# V8.net
KiCad netlist of a schematic drawn in Altium Designer
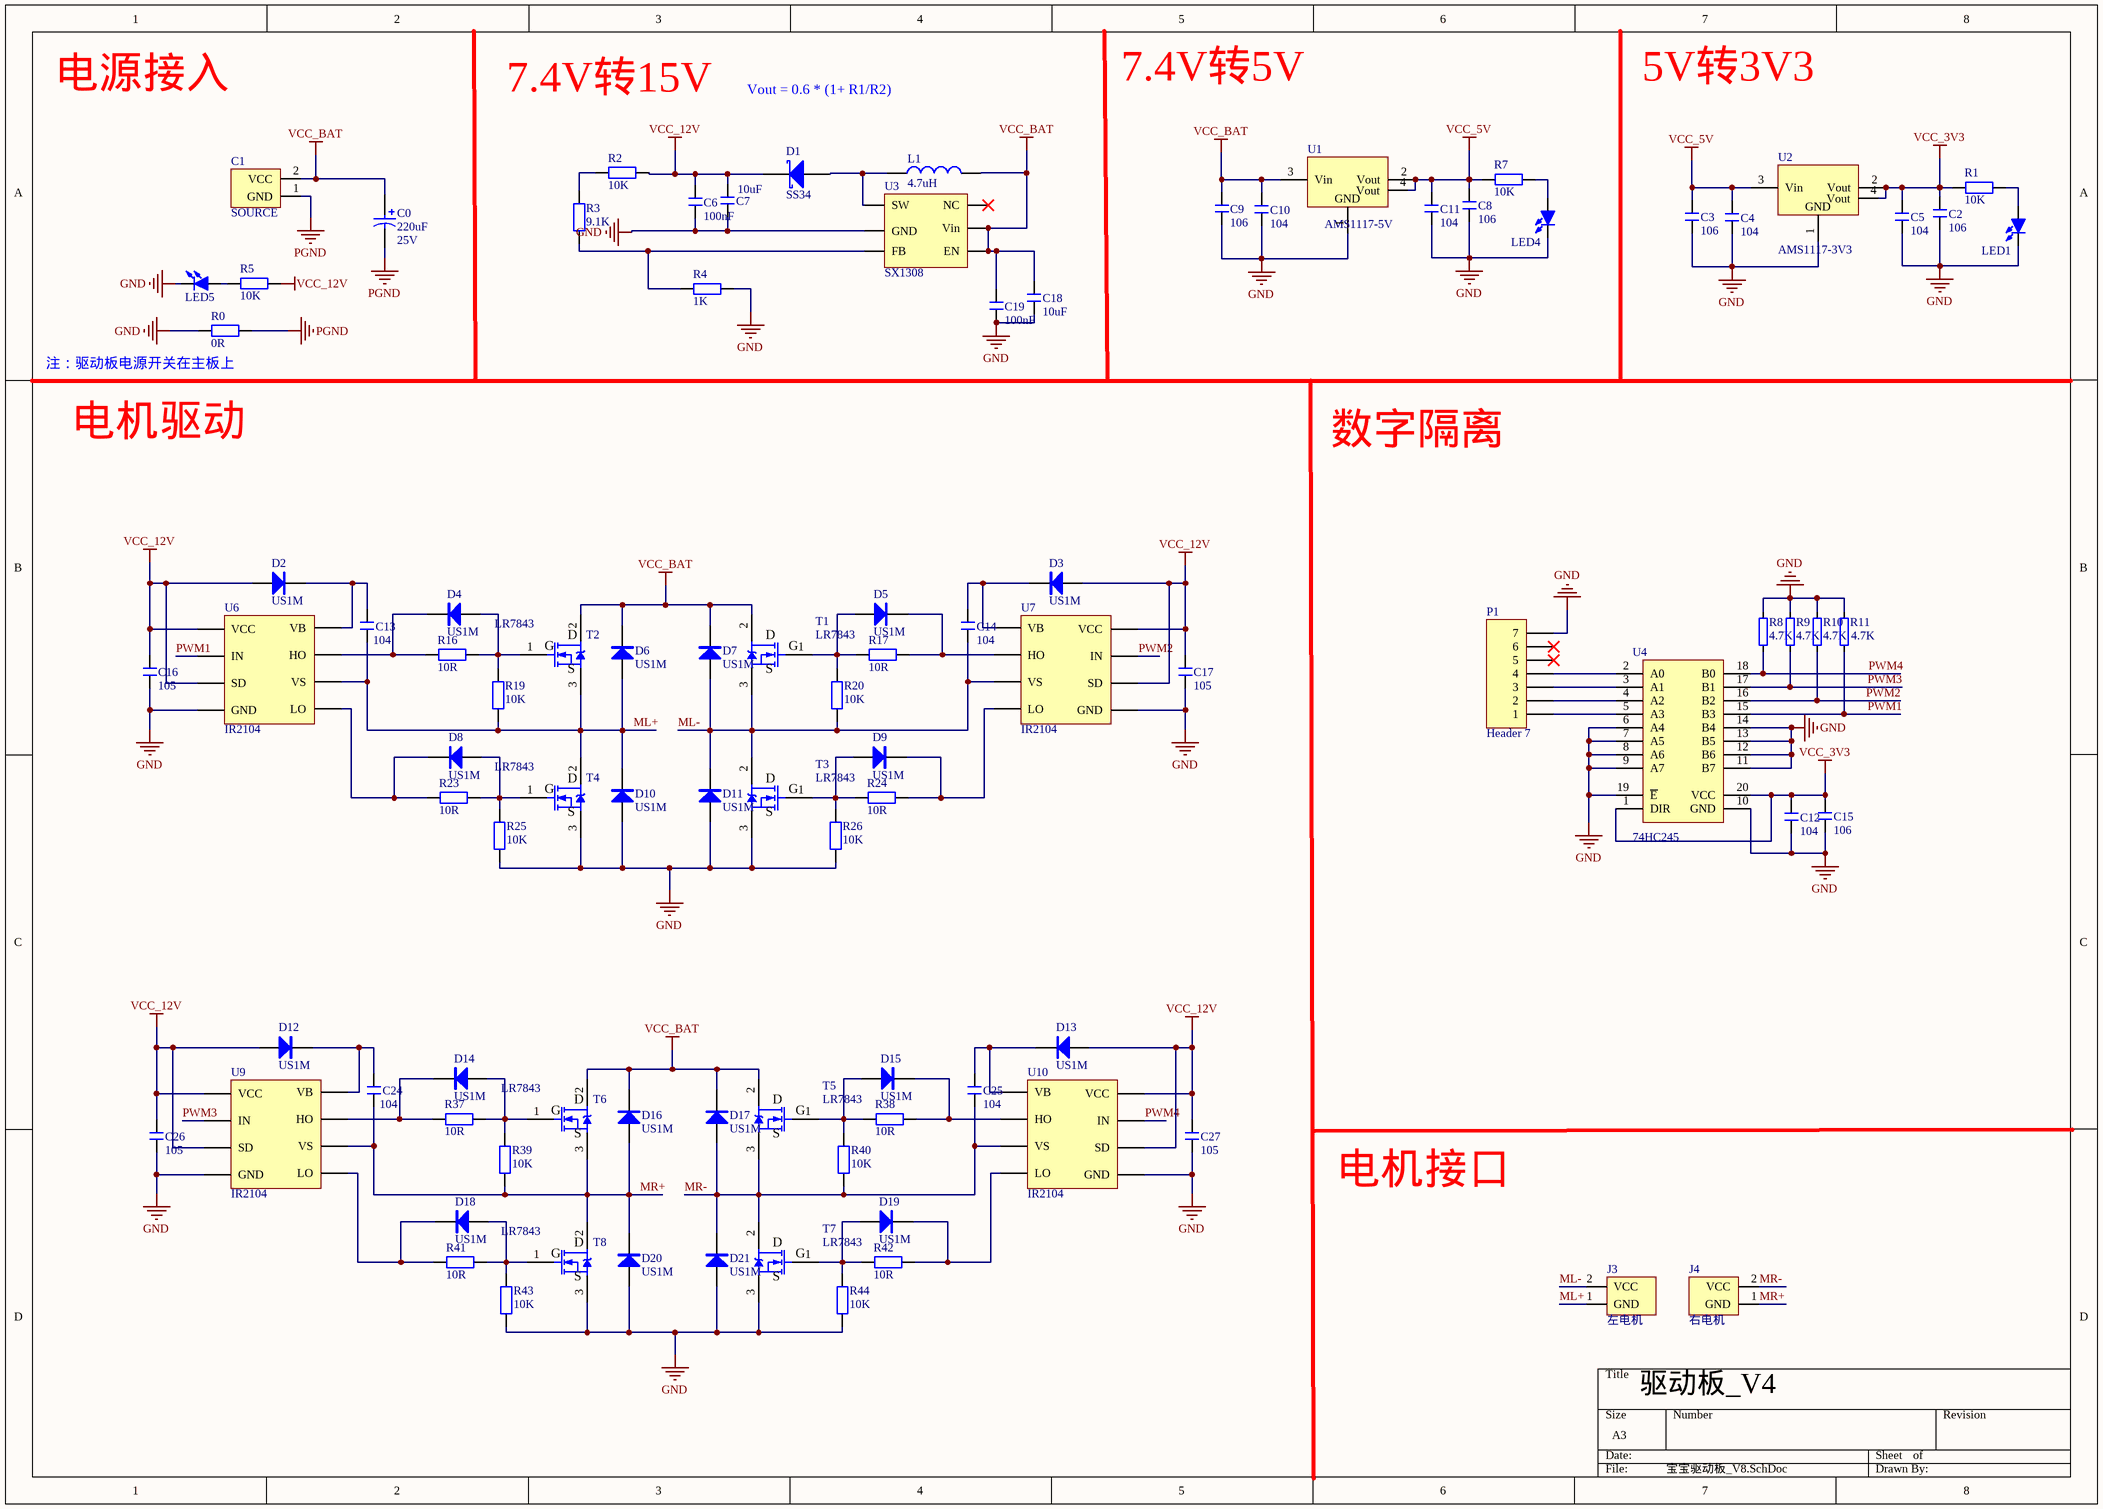
[diagram p0: 宝宝驱动板_V8.SchDoc]

(export (version "E")
  (design (tool "Eeschema 10.0.6"))
  (components
    (comp (ref "C0")
      (value "220uF")
      (footprint "CAPPR3.5-8X11.5")
      (description "Polarized Capacitor (Radial)")
      (fields
        (field (name "VOLTAGE") "25V")
        (field (name "Comment") "220uF 25V")
        (field (name "PUBLISHER") "Altium Limited")
      )
      (libsource (lib "驱动板_V6") (part "Cap-Elect"))
    )
    (comp (ref "C1")
      (value "SOURCE")
      (footprint "KF128-5.08-2P")
      (libsource (lib "飞思-AI原理图库") (part "Source_端子"))
    )
    (comp (ref "C2")
      (value "106")
      (footprint "C 0603_M")
      (description "贴片电容")
      (libsource (lib "视觉原理图库") (part "C"))
    )
    (comp (ref "C3")
      (value "106")
      (footprint "C 0603_M")
      (description "贴片电容")
      (libsource (lib "视觉原理图库") (part "C"))
    )
    (comp (ref "C4")
      (value "104")
      (footprint "C 0603_M")
      (description "贴片电容")
      (libsource (lib "视觉原理图库") (part "C"))
    )
    (comp (ref "C5")
      (value "104")
      (footprint "C 0603_M")
      (description "贴片电容")
      (libsource (lib "视觉原理图库") (part "C"))
    )
    (comp (ref "C6")
      (value "100nF")
      (footprint "C 0603_M")
      (description "贴片电容")
      (libsource (lib "视觉原理图库") (part "C"))
    )
    (comp (ref "C7")
      (value "10uF")
      (footprint "C 0603_M")
      (description "贴片电容")
      (libsource (lib "视觉原理图库") (part "C"))
    )
    (comp (ref "C8")
      (value "106")
      (footprint "C 0603_M")
      (description "贴片电容")
      (libsource (lib "视觉原理图库") (part "C"))
    )
    (comp (ref "C9")
      (value "106")
      (footprint "C 0603_M")
      (description "贴片电容")
      (libsource (lib "视觉原理图库") (part "C"))
    )
    (comp (ref "C10")
      (value "104")
      (footprint "C 0603_M")
      (description "贴片电容")
      (libsource (lib "视觉原理图库") (part "C"))
    )
    (comp (ref "C11")
      (value "104")
      (footprint "C 0603_M")
      (description "贴片电容")
      (libsource (lib "视觉原理图库") (part "C"))
    )
    (comp (ref "C12")
      (value "104")
      (footprint "C 0603_M")
      (description "贴片电容")
      (libsource (lib "视觉原理图库") (part "C"))
    )
    (comp (ref "C13")
      (value "104")
      (footprint "C 0603_M")
      (description "贴片陶瓷电容 MLCC")
      (libsource (lib "视觉原理图库") (part "C"))
    )
    (comp (ref "C14")
      (value "104")
      (footprint "C 0603_M")
      (description "贴片陶瓷电容 MLCC")
      (libsource (lib "视觉原理图库") (part "C"))
    )
    (comp (ref "C15")
      (value "106")
      (footprint "C 0603_M")
      (description "贴片电容")
      (libsource (lib "视觉原理图库") (part "C"))
    )
    (comp (ref "C16")
      (value "105")
      (footprint "C 0603_M")
      (description "贴片电容")
      (libsource (lib "视觉原理图库") (part "C"))
    )
    (comp (ref "C17")
      (value "105")
      (footprint "C 0603_M")
      (description "贴片电容")
      (libsource (lib "视觉原理图库") (part "C"))
    )
    (comp (ref "C18")
      (value "10uF")
      (footprint "C 0603_M")
      (description "贴片电容")
      (libsource (lib "视觉原理图库") (part "C"))
    )
    (comp (ref "C19")
      (value "100nF")
      (footprint "C 0603_M")
      (description "贴片电容")
      (libsource (lib "视觉原理图库") (part "C"))
    )
    (comp (ref "C24")
      (value "104")
      (footprint "C 0603_M")
      (description "贴片陶瓷电容 MLCC")
      (libsource (lib "视觉原理图库") (part "C"))
    )
    (comp (ref "C25")
      (value "104")
      (footprint "C 0603_M")
      (description "贴片陶瓷电容 MLCC")
      (libsource (lib "视觉原理图库") (part "C"))
    )
    (comp (ref "C26")
      (value "105")
      (footprint "C 0603_M")
      (description "贴片电容")
      (libsource (lib "视觉原理图库") (part "C"))
    )
    (comp (ref "C27")
      (value "105")
      (footprint "C 0603_M")
      (description "贴片电容")
      (libsource (lib "视觉原理图库") (part "C"))
    )
    (comp (ref "D1")
      (value "SS34")
      (footprint "SMA")
      (description "肖特基二极管")
      (libsource (lib "视觉原理图库") (part "SS34"))
    )
    (comp (ref "D2")
      (value "US1M")
      (footprint "SMA")
      (description "快恢复二极管")
      (libsource (lib "视觉原理图库") (part "US1M"))
    )
    (comp (ref "D3")
      (value "US1M")
      (footprint "SMA")
      (description "快恢复二极管")
      (libsource (lib "视觉原理图库") (part "US1M"))
    )
    (comp (ref "D4")
      (value "US1M")
      (footprint "SMA")
      (description "快恢复二极管")
      (libsource (lib "视觉原理图库") (part "US1M"))
    )
    (comp (ref "D5")
      (value "US1M")
      (footprint "SMA")
      (description "快恢复二极管")
      (libsource (lib "视觉原理图库") (part "US1M"))
    )
    (comp (ref "D6")
      (value "US1M")
      (footprint "SMA")
      (description "快恢复二极管")
      (libsource (lib "视觉原理图库") (part "US1M"))
    )
    (comp (ref "D7")
      (value "US1M")
      (footprint "SMA")
      (description "快恢复二极管")
      (libsource (lib "视觉原理图库") (part "US1M"))
    )
    (comp (ref "D8")
      (value "US1M")
      (footprint "SMA")
      (description "快恢复二极管")
      (libsource (lib "视觉原理图库") (part "US1M"))
    )
    (comp (ref "D9")
      (value "US1M")
      (footprint "SMA")
      (description "快恢复二极管")
      (libsource (lib "视觉原理图库") (part "US1M"))
    )
    (comp (ref "D10")
      (value "US1M")
      (footprint "SMA")
      (description "快恢复二极管")
      (libsource (lib "视觉原理图库") (part "US1M"))
    )
    (comp (ref "D11")
      (value "US1M")
      (footprint "SMA")
      (description "快恢复二极管")
      (libsource (lib "视觉原理图库") (part "US1M"))
    )
    (comp (ref "D12")
      (value "US1M")
      (footprint "SMA")
      (description "快恢复二极管")
      (libsource (lib "视觉原理图库") (part "US1M"))
    )
    (comp (ref "D13")
      (value "US1M")
      (footprint "SMA")
      (description "快恢复二极管")
      (libsource (lib "视觉原理图库") (part "US1M"))
    )
    (comp (ref "D14")
      (value "US1M")
      (footprint "SMA")
      (description "快恢复二极管")
      (libsource (lib "视觉原理图库") (part "US1M"))
    )
    (comp (ref "D15")
      (value "US1M")
      (footprint "SMA")
      (description "快恢复二极管")
      (libsource (lib "视觉原理图库") (part "US1M"))
    )
    (comp (ref "D16")
      (value "US1M")
      (footprint "SMA")
      (description "快恢复二极管")
      (libsource (lib "视觉原理图库") (part "US1M"))
    )
    (comp (ref "D17")
      (value "US1M")
      (footprint "SMA")
      (description "快恢复二极管")
      (libsource (lib "视觉原理图库") (part "US1M"))
    )
    (comp (ref "D18")
      (value "US1M")
      (footprint "SMA")
      (description "快恢复二极管")
      (libsource (lib "视觉原理图库") (part "US1M"))
    )
    (comp (ref "D19")
      (value "US1M")
      (footprint "SMA")
      (description "快恢复二极管")
      (libsource (lib "视觉原理图库") (part "US1M"))
    )
    (comp (ref "D20")
      (value "US1M")
      (footprint "SMA")
      (description "快恢复二极管")
      (libsource (lib "视觉原理图库") (part "US1M"))
    )
    (comp (ref "D21")
      (value "US1M")
      (footprint "SMA")
      (description "快恢复二极管")
      (libsource (lib "视觉原理图库") (part "US1M"))
    )
    (comp (ref "J3") (value "左电机") (footprint "KF128-5.08-2P") (libsource (lib "") (part "接线端子_1")))
    (comp (ref "J4") (value "右电机") (footprint "KF128-5.08-2P") (libsource (lib "视觉原理图库") (part "接线端子")))
    (comp (ref "L1")
      (value "4.7uH")
      (footprint "L 7*7")
      (description "功率电感")
      (libsource (lib "视觉原理图库") (part "L"))
    )
    (comp (ref "LED1")
      (value "红色")
      (footprint "LED 0603")
      (description "贴片LED")
      (fields (field (name "版权归属") "封装库来自淘宝 ID：黄晶宝石"))
      (libsource (lib "视觉原理图库") (part "LED"))
    )
    (comp (ref "LED4")
      (value "红色")
      (footprint "LED 0603")
      (description "贴片LED")
      (fields (field (name "版权归属") "封装库来自淘宝 ID：黄晶宝石"))
      (libsource (lib "视觉原理图库") (part "LED"))
    )
    (comp (ref "LED5")
      (value "红色")
      (footprint "LED 0603")
      (description "贴片LED")
      (fields (field (name "版权归属") "封装库来自淘宝 ID：黄晶宝石"))
      (libsource (lib "视觉原理图库") (part "LED"))
    )
    (comp (ref "P1")
      (value "Header 7")
      (footprint "PH2.0-L-Z-7P")
      (description "Header, 7-Pin")
      (fields (field (name "PUBLISHER") "Altium Limited"))
      (libsource (lib "Miscellaneous Connectors") (part "Header 7"))
    )
    (comp (ref "R0")
      (value "0R")
      (footprint "R 2512_M")
      (description "贴片电阻")
      (fields (field (name "Comment") "R") (field (name "版权归属") "电协硬件组"))
      (libsource (lib "3.1   - 电阻-电容-电感") (part "R"))
    )
    (comp (ref "R1")
      (value "10K")
      (footprint "R 0603_M")
      (description "贴片电阻")
      (fields (field (name "版权归属") "来自淘宝 ID：黄晶宝石"))
      (libsource (lib "视觉原理图库") (part "R"))
    )
    (comp (ref "R2")
      (value "10K")
      (footprint "R 0603_M")
      (description "贴片电阻")
      (fields (field (name "版权归属") "来自淘宝 ID：黄晶宝石"))
      (libsource (lib "视觉原理图库") (part "R"))
    )
    (comp (ref "R3")
      (value "9.1K")
      (footprint "R 0603_M")
      (description "贴片电阻")
      (fields (field (name "版权归属") "来自淘宝 ID：黄晶宝石"))
      (libsource (lib "视觉原理图库") (part "R"))
    )
    (comp (ref "R4")
      (value "1K")
      (footprint "R 0603_M")
      (description "贴片电阻")
      (fields (field (name "版权归属") "来自淘宝 ID：黄晶宝石"))
      (libsource (lib "视觉原理图库") (part "R"))
    )
    (comp (ref "R5")
      (value "10K")
      (footprint "R 0603_M")
      (description "贴片电阻")
      (fields (field (name "版权归属") "来自淘宝 ID：黄晶宝石"))
      (libsource (lib "视觉原理图库") (part "R"))
    )
    (comp (ref "R7")
      (value "10K")
      (footprint "R 0603_M")
      (description "贴片电阻")
      (fields (field (name "版权归属") "来自淘宝 ID：黄晶宝石"))
      (libsource (lib "视觉原理图库") (part "R"))
    )
    (comp (ref "R8") (value "4.7K") (footprint "R 0603_M") (libsource (lib "驱动板--原理图") (part "RES")))
    (comp (ref "R9") (value "4.7K") (footprint "R 0603_M") (libsource (lib "驱动板--原理图") (part "RES")))
    (comp (ref "R10") (value "4.7K") (footprint "R 0603_M") (libsource (lib "驱动板--原理图") (part "RES")))
    (comp (ref "R11") (value "4.7K") (footprint "R 0603_M") (libsource (lib "驱动板--原理图") (part "RES")))
    (comp (ref "R16")
      (value "10R")
      (footprint "R 0603_M")
      (description "贴片电阻")
      (fields (field (name "版权归属") "来自淘宝 ID：黄晶宝石"))
      (libsource (lib "视觉原理图库") (part "R"))
    )
    (comp (ref "R17")
      (value "10R")
      (footprint "R 0603_M")
      (description "贴片电阻")
      (fields (field (name "版权归属") "来自淘宝 ID：黄晶宝石"))
      (libsource (lib "视觉原理图库") (part "R"))
    )
    (comp (ref "R19")
      (value "10K")
      (footprint "R 0603_M")
      (description "贴片电阻")
      (fields (field (name "版权归属") "来自淘宝 ID：黄晶宝石"))
      (libsource (lib "视觉原理图库") (part "R"))
    )
    (comp (ref "R20")
      (value "10K")
      (footprint "R 0603_M")
      (description "贴片电阻")
      (fields (field (name "版权归属") "来自淘宝 ID：黄晶宝石"))
      (libsource (lib "视觉原理图库") (part "R"))
    )
    (comp (ref "R23")
      (value "10R")
      (footprint "R 0603_M")
      (description "贴片电阻")
      (fields (field (name "版权归属") "来自淘宝 ID：黄晶宝石"))
      (libsource (lib "视觉原理图库") (part "R"))
    )
    (comp (ref "R24")
      (value "10R")
      (footprint "R 0603_M")
      (description "贴片电阻")
      (fields (field (name "版权归属") "来自淘宝 ID：黄晶宝石"))
      (libsource (lib "视觉原理图库") (part "R"))
    )
    (comp (ref "R25")
      (value "10K")
      (footprint "R 0603_M")
      (description "贴片电阻")
      (fields (field (name "版权归属") "来自淘宝 ID：黄晶宝石"))
      (libsource (lib "视觉原理图库") (part "R"))
    )
    (comp (ref "R26")
      (value "10K")
      (footprint "R 0603_M")
      (description "贴片电阻")
      (fields (field (name "版权归属") "来自淘宝 ID：黄晶宝石"))
      (libsource (lib "视觉原理图库") (part "R"))
    )
    (comp (ref "R37")
      (value "10R")
      (footprint "R 0603_M")
      (description "贴片电阻")
      (fields (field (name "版权归属") "来自淘宝 ID：黄晶宝石"))
      (libsource (lib "视觉原理图库") (part "R"))
    )
    (comp (ref "R38")
      (value "10R")
      (footprint "R 0603_M")
      (description "贴片电阻")
      (fields (field (name "版权归属") "来自淘宝 ID：黄晶宝石"))
      (libsource (lib "视觉原理图库") (part "R"))
    )
    (comp (ref "R39")
      (value "10K")
      (footprint "R 0603_M")
      (description "贴片电阻")
      (fields (field (name "版权归属") "来自淘宝 ID：黄晶宝石"))
      (libsource (lib "视觉原理图库") (part "R"))
    )
    (comp (ref "R40")
      (value "10K")
      (footprint "R 0603_M")
      (description "贴片电阻")
      (fields (field (name "版权归属") "来自淘宝 ID：黄晶宝石"))
      (libsource (lib "视觉原理图库") (part "R"))
    )
    (comp (ref "R41")
      (value "10R")
      (footprint "R 0603_M")
      (description "贴片电阻")
      (fields (field (name "版权归属") "来自淘宝 ID：黄晶宝石"))
      (libsource (lib "视觉原理图库") (part "R"))
    )
    (comp (ref "R42")
      (value "10R")
      (footprint "R 0603_M")
      (description "贴片电阻")
      (fields (field (name "版权归属") "来自淘宝 ID：黄晶宝石"))
      (libsource (lib "视觉原理图库") (part "R"))
    )
    (comp (ref "R43")
      (value "10K")
      (footprint "R 0603_M")
      (description "贴片电阻")
      (fields (field (name "版权归属") "来自淘宝 ID：黄晶宝石"))
      (libsource (lib "视觉原理图库") (part "R"))
    )
    (comp (ref "R44")
      (value "10K")
      (footprint "R 0603_M")
      (description "贴片电阻")
      (fields (field (name "版权归属") "来自淘宝 ID：黄晶宝石"))
      (libsource (lib "视觉原理图库") (part "R"))
    )
    (comp (ref "T1")
      (value "LR7843")
      (footprint "TO252")
      (description "N-MOS")
      (libsource (lib "视觉原理图库") (part "SM3113NSUC"))
    )
    (comp (ref "T2")
      (value "LR7843")
      (footprint "TO252")
      (description "N-MOS")
      (libsource (lib "视觉原理图库") (part "SM3113NSUC"))
    )
    (comp (ref "T3")
      (value "LR7843")
      (footprint "TO252")
      (description "N-MOS")
      (libsource (lib "视觉原理图库") (part "SM3113NSUC"))
    )
    (comp (ref "T4")
      (value "LR7843")
      (footprint "TO252")
      (description "N-MOS")
      (libsource (lib "视觉原理图库") (part "SM3113NSUC"))
    )
    (comp (ref "T5")
      (value "LR7843")
      (footprint "TO252")
      (description "N-MOS")
      (libsource (lib "视觉原理图库") (part "SM3113NSUC"))
    )
    (comp (ref "T6")
      (value "LR7843")
      (footprint "TO252")
      (description "N-MOS")
      (libsource (lib "视觉原理图库") (part "SM3113NSUC"))
    )
    (comp (ref "T7")
      (value "LR7843")
      (footprint "TO252")
      (description "N-MOS")
      (libsource (lib "视觉原理图库") (part "SM3113NSUC"))
    )
    (comp (ref "T8")
      (value "LR7843")
      (footprint "TO252")
      (description "N-MOS")
      (libsource (lib "视觉原理图库") (part "SM3113NSUC"))
    )
    (comp (ref "U1")
      (value "AMS1117-5V")
      (footprint "SOT223_L")
      (description "三端稳压芯片")
      (libsource (lib "视觉原理图库") (part "AMS1117"))
    )
    (comp (ref "U2")
      (value "AMS1117-3V3")
      (footprint "SOT223_L")
      (description "三端稳压芯片")
      (libsource (lib "视觉原理图库") (part "AMS1117"))
    )
    (comp (ref "U3")
      (value "SX1308")
      (footprint "SOT23-6")
      (description "DCDC升压芯片")
      (libsource (lib "视觉原理图库") (part "SX1308"))
    )
    (comp (ref "U4")
      (value "74HC245")
      (footprint "SOP20Z_M")
      (description "光耦隔离")
      (libsource (lib "驱动板_V5") (part "74HC245"))
    )
    (comp (ref "U6")
      (value "IR2104")
      (footprint "SOP8")
      (description "半桥驱动芯片")
      (libsource (lib "视觉原理图库") (part "EG2104"))
    )
    (comp (ref "U7")
      (value "IR2104")
      (footprint "SOP8")
      (description "半桥驱动芯片")
      (libsource (lib "") (part "EG2104_1"))
    )
    (comp (ref "U9")
      (value "IR2104")
      (footprint "SOP8")
      (description "半桥驱动芯片")
      (libsource (lib "视觉原理图库") (part "EG2104"))
    )
    (comp (ref "U10")
      (value "IR2104")
      (footprint "SOP8")
      (description "半桥驱动芯片")
      (libsource (lib "") (part "EG2104_1"))
    )
  )
  (nets
    (net (code "1") (name "/ML+") (class "Default")
      (node (ref "C13") (pin "1") (pinfunction "1_1") (pintype "passive"))
      (node (ref "D10") (pin "2") (pinfunction "K_2") (pintype "passive"))
      (node (ref "D6") (pin "1") (pinfunction "A_1") (pintype "passive"))
      (node (ref "J3") (pin "1") (pinfunction "GND_1") (pintype "passive"))
      (node (ref "R19") (pin "1") (pinfunction "1_1") (pintype "passive"))
      (node (ref "T2") (pin "3") (pinfunction "S_3") (pintype "passive"))
      (node (ref "T4") (pin "2") (pinfunction "D_2") (pintype "passive"))
      (node (ref "U6") (pin "6") (pinfunction "VS_6") (pintype "passive"))
    )
    (net (code "2") (name "/ML-") (class "Default")
      (node (ref "C14") (pin "1") (pinfunction "1_1") (pintype "passive"))
      (node (ref "D11") (pin "2") (pinfunction "K_2") (pintype "passive"))
      (node (ref "D7") (pin "1") (pinfunction "A_1") (pintype "passive"))
      (node (ref "J3") (pin "2") (pinfunction "VCC_2") (pintype "passive"))
      (node (ref "R20") (pin "1") (pinfunction "1_1") (pintype "passive"))
      (node (ref "T1") (pin "3") (pinfunction "S_3") (pintype "passive"))
      (node (ref "T3") (pin "2") (pinfunction "D_2") (pintype "passive"))
      (node (ref "U7") (pin "6") (pinfunction "VS_6") (pintype "passive"))
    )
    (net (code "3") (name "/MR+") (class "Default")
      (node (ref "C24") (pin "1") (pinfunction "1_1") (pintype "passive"))
      (node (ref "D16") (pin "1") (pinfunction "A_1") (pintype "passive"))
      (node (ref "D20") (pin "2") (pinfunction "K_2") (pintype "passive"))
      (node (ref "J4") (pin "1") (pinfunction "GND_1") (pintype "passive"))
      (node (ref "R39") (pin "1") (pinfunction "1_1") (pintype "passive"))
      (node (ref "T6") (pin "3") (pinfunction "S_3") (pintype "passive"))
      (node (ref "T8") (pin "2") (pinfunction "D_2") (pintype "passive"))
      (node (ref "U9") (pin "6") (pinfunction "VS_6") (pintype "passive"))
    )
    (net (code "4") (name "/MR-") (class "Default")
      (node (ref "C25") (pin "1") (pinfunction "1_1") (pintype "passive"))
      (node (ref "D17") (pin "1") (pinfunction "A_1") (pintype "passive"))
      (node (ref "D21") (pin "2") (pinfunction "K_2") (pintype "passive"))
      (node (ref "J4") (pin "2") (pinfunction "VCC_2") (pintype "passive"))
      (node (ref "R40") (pin "1") (pinfunction "1_1") (pintype "passive"))
      (node (ref "T5") (pin "3") (pinfunction "S_3") (pintype "passive"))
      (node (ref "T7") (pin "2") (pinfunction "D_2") (pintype "passive"))
      (node (ref "U10") (pin "6") (pinfunction "VS_6") (pintype "passive"))
    )
    (net (code "5") (name "/PWM1") (class "Default")
      (node (ref "R11") (pin "1") (pinfunction "1_1") (pintype "passive"))
      (node (ref "U4") (pin "15") (pinfunction "B3_15") (pintype "passive"))
      (node (ref "U6") (pin "2") (pinfunction "IN_2") (pintype "passive"))
    )
    (net (code "6") (name "/PWM2") (class "Default")
      (node (ref "R10") (pin "1") (pinfunction "1_1") (pintype "passive"))
      (node (ref "U4") (pin "16") (pinfunction "B2_16") (pintype "passive"))
      (node (ref "U7") (pin "2") (pinfunction "IN_2") (pintype "passive"))
    )
    (net (code "7") (name "/PWM3") (class "Default")
      (node (ref "R9") (pin "1") (pinfunction "1_1") (pintype "passive"))
      (node (ref "U4") (pin "17") (pinfunction "B1_17") (pintype "passive"))
      (node (ref "U9") (pin "2") (pinfunction "IN_2") (pintype "passive"))
    )
    (net (code "8") (name "/PWM4") (class "Default")
      (node (ref "R8") (pin "1") (pinfunction "1_1") (pintype "passive"))
      (node (ref "U10") (pin "2") (pinfunction "IN_2") (pintype "passive"))
      (node (ref "U4") (pin "18") (pinfunction "B0_18") (pintype "passive"))
    )
    (net (code "9") (name "GND") (class "Default")
      (node (ref "C10") (pin "1") (pinfunction "1_1") (pintype "passive"))
      (node (ref "C11") (pin "1") (pinfunction "1_1") (pintype "passive"))
      (node (ref "C12") (pin "1") (pinfunction "1_1") (pintype "passive"))
      (node (ref "C15") (pin "1") (pinfunction "1_1") (pintype "passive"))
      (node (ref "C16") (pin "1") (pinfunction "1_1") (pintype "passive"))
      (node (ref "C17") (pin "1") (pinfunction "1_1") (pintype "passive"))
      (node (ref "C18") (pin "1") (pinfunction "1_1") (pintype "passive"))
      (node (ref "C19") (pin "1") (pinfunction "1_1") (pintype "passive"))
      (node (ref "C2") (pin "1") (pinfunction "1_1") (pintype "passive"))
      (node (ref "C26") (pin "1") (pinfunction "1_1") (pintype "passive"))
      (node (ref "C27") (pin "1") (pinfunction "1_1") (pintype "passive"))
      (node (ref "C3") (pin "1") (pinfunction "1_1") (pintype "passive"))
      (node (ref "C4") (pin "1") (pinfunction "1_1") (pintype "passive"))
      (node (ref "C5") (pin "1") (pinfunction "1_1") (pintype "passive"))
      (node (ref "C6") (pin "1") (pinfunction "1_1") (pintype "passive"))
      (node (ref "C7") (pin "1") (pinfunction "1_1") (pintype "passive"))
      (node (ref "C8") (pin "1") (pinfunction "1_1") (pintype "passive"))
      (node (ref "C9") (pin "1") (pinfunction "1_1") (pintype "passive"))
      (node (ref "D10") (pin "1") (pinfunction "A_1") (pintype "passive"))
      (node (ref "D11") (pin "1") (pinfunction "A_1") (pintype "passive"))
      (node (ref "D20") (pin "1") (pinfunction "A_1") (pintype "passive"))
      (node (ref "D21") (pin "1") (pinfunction "A_1") (pintype "passive"))
      (node (ref "LED1") (pin "2") (pinfunction "K_2") (pintype "passive"))
      (node (ref "LED4") (pin "2") (pinfunction "K_2") (pintype "passive"))
      (node (ref "LED5") (pin "2") (pinfunction "K_2") (pintype "passive"))
      (node (ref "P1") (pin "7") (pinfunction "7_7") (pintype "passive"))
      (node (ref "R0") (pin "1") (pinfunction "1_1") (pintype "passive"))
      (node (ref "R10") (pin "2") (pinfunction "2_2") (pintype "passive"))
      (node (ref "R11") (pin "2") (pinfunction "2_2") (pintype "passive"))
      (node (ref "R25") (pin "1") (pinfunction "1_1") (pintype "passive"))
      (node (ref "R26") (pin "1") (pinfunction "1_1") (pintype "passive"))
      (node (ref "R4") (pin "1") (pinfunction "1_1") (pintype "passive"))
      (node (ref "R43") (pin "1") (pinfunction "1_1") (pintype "passive"))
      (node (ref "R44") (pin "1") (pinfunction "1_1") (pintype "passive"))
      (node (ref "R8") (pin "2") (pinfunction "2_2") (pintype "passive"))
      (node (ref "R9") (pin "2") (pinfunction "2_2") (pintype "passive"))
      (node (ref "T3") (pin "3") (pinfunction "S_3") (pintype "passive"))
      (node (ref "T4") (pin "3") (pinfunction "S_3") (pintype "passive"))
      (node (ref "T7") (pin "3") (pinfunction "S_3") (pintype "passive"))
      (node (ref "T8") (pin "3") (pinfunction "S_3") (pintype "passive"))
      (node (ref "U1") (pin "1") (pinfunction "GND_1") (pintype "passive"))
      (node (ref "U10") (pin "4") (pinfunction "GND_4") (pintype "passive"))
      (node (ref "U2") (pin "1") (pinfunction "GND_1") (pintype "passive"))
      (node (ref "U3") (pin "2") (pinfunction "GND_2") (pintype "passive"))
      (node (ref "U4") (pin "10") (pinfunction "GND_10") (pintype "passive"))
      (node (ref "U4") (pin "11") (pinfunction "B7_11") (pintype "passive"))
      (node (ref "U4") (pin "12") (pinfunction "B6_12") (pintype "passive"))
      (node (ref "U4") (pin "13") (pinfunction "B5_13") (pintype "passive"))
      (node (ref "U4") (pin "14") (pinfunction "B4_14") (pintype "passive"))
      (node (ref "U4") (pin "19") (pinfunction "~{E}_19") (pintype "passive"))
      (node (ref "U4") (pin "6") (pinfunction "A4_6") (pintype "passive"))
      (node (ref "U4") (pin "7") (pinfunction "A5_7") (pintype "passive"))
      (node (ref "U4") (pin "8") (pinfunction "A6_8") (pintype "passive"))
      (node (ref "U4") (pin "9") (pinfunction "A7_9") (pintype "passive"))
      (node (ref "U6") (pin "4") (pinfunction "GND_4") (pintype "passive"))
      (node (ref "U7") (pin "4") (pinfunction "GND_4") (pintype "passive"))
      (node (ref "U9") (pin "4") (pinfunction "GND_4") (pintype "passive"))
    )
    (net (code "10") (name "Net-(D1-A)") (class "Default")
      (node (ref "D1") (pin "1") (pinfunction "A_1") (pintype "passive"))
      (node (ref "L1") (pin "1") (pinfunction "1_1") (pintype "passive"))
      (node (ref "U3") (pin "1") (pinfunction "SW_1") (pintype "passive"))
    )
    (net (code "11") (name "Net-(D2-K)") (class "Default")
      (node (ref "C13") (pin "2") (pinfunction "2_2") (pintype "passive"))
      (node (ref "D2") (pin "2") (pinfunction "K_2") (pintype "passive"))
      (node (ref "U6") (pin "8") (pinfunction "VB_8") (pintype "passive"))
    )
    (net (code "12") (name "Net-(D3-K)") (class "Default")
      (node (ref "C14") (pin "2") (pinfunction "2_2") (pintype "passive"))
      (node (ref "D3") (pin "2") (pinfunction "K_2") (pintype "passive"))
      (node (ref "U7") (pin "8") (pinfunction "VB_8") (pintype "passive"))
    )
    (net (code "13") (name "Net-(D4-A)") (class "Default")
      (node (ref "D4") (pin "1") (pinfunction "A_1") (pintype "passive"))
      (node (ref "R16") (pin "2") (pinfunction "2_2") (pintype "passive"))
      (node (ref "R19") (pin "2") (pinfunction "2_2") (pintype "passive"))
      (node (ref "T2") (pin "1") (pinfunction "G_1") (pintype "passive"))
    )
    (net (code "14") (name "Net-(D4-K)") (class "Default")
      (node (ref "D4") (pin "2") (pinfunction "K_2") (pintype "passive"))
      (node (ref "R16") (pin "1") (pinfunction "1_1") (pintype "passive"))
      (node (ref "U6") (pin "7") (pinfunction "HO_7") (pintype "passive"))
    )
    (net (code "15") (name "Net-(D5-A)") (class "Default")
      (node (ref "D5") (pin "1") (pinfunction "A_1") (pintype "passive"))
      (node (ref "R17") (pin "2") (pinfunction "2_2") (pintype "passive"))
      (node (ref "R20") (pin "2") (pinfunction "2_2") (pintype "passive"))
      (node (ref "T1") (pin "1") (pinfunction "G_1") (pintype "passive"))
    )
    (net (code "16") (name "Net-(D5-K)") (class "Default")
      (node (ref "D5") (pin "2") (pinfunction "K_2") (pintype "passive"))
      (node (ref "R17") (pin "1") (pinfunction "1_1") (pintype "passive"))
      (node (ref "U7") (pin "7") (pinfunction "HO_7") (pintype "passive"))
    )
    (net (code "17") (name "Net-(D8-A)") (class "Default")
      (node (ref "D8") (pin "1") (pinfunction "A_1") (pintype "passive"))
      (node (ref "R23") (pin "2") (pinfunction "2_2") (pintype "passive"))
      (node (ref "R25") (pin "2") (pinfunction "2_2") (pintype "passive"))
      (node (ref "T4") (pin "1") (pinfunction "G_1") (pintype "passive"))
    )
    (net (code "18") (name "Net-(D8-K)") (class "Default")
      (node (ref "D8") (pin "2") (pinfunction "K_2") (pintype "passive"))
      (node (ref "R23") (pin "1") (pinfunction "1_1") (pintype "passive"))
      (node (ref "U6") (pin "5") (pinfunction "LO_5") (pintype "passive"))
    )
    (net (code "19") (name "Net-(D9-A)") (class "Default")
      (node (ref "D9") (pin "1") (pinfunction "A_1") (pintype "passive"))
      (node (ref "R24") (pin "2") (pinfunction "2_2") (pintype "passive"))
      (node (ref "R26") (pin "2") (pinfunction "2_2") (pintype "passive"))
      (node (ref "T3") (pin "1") (pinfunction "G_1") (pintype "passive"))
    )
    (net (code "20") (name "Net-(D9-K)") (class "Default")
      (node (ref "D9") (pin "2") (pinfunction "K_2") (pintype "passive"))
      (node (ref "R24") (pin "1") (pinfunction "1_1") (pintype "passive"))
      (node (ref "U7") (pin "5") (pinfunction "LO_5") (pintype "passive"))
    )
    (net (code "21") (name "Net-(D12-K)") (class "Default")
      (node (ref "C24") (pin "2") (pinfunction "2_2") (pintype "passive"))
      (node (ref "D12") (pin "2") (pinfunction "K_2") (pintype "passive"))
      (node (ref "U9") (pin "8") (pinfunction "VB_8") (pintype "passive"))
    )
    (net (code "22") (name "Net-(D13-K)") (class "Default")
      (node (ref "C25") (pin "2") (pinfunction "2_2") (pintype "passive"))
      (node (ref "D13") (pin "2") (pinfunction "K_2") (pintype "passive"))
      (node (ref "U10") (pin "8") (pinfunction "VB_8") (pintype "passive"))
    )
    (net (code "23") (name "Net-(D14-A)") (class "Default")
      (node (ref "D14") (pin "1") (pinfunction "A_1") (pintype "passive"))
      (node (ref "R37") (pin "2") (pinfunction "2_2") (pintype "passive"))
      (node (ref "R39") (pin "2") (pinfunction "2_2") (pintype "passive"))
      (node (ref "T6") (pin "1") (pinfunction "G_1") (pintype "passive"))
    )
    (net (code "24") (name "Net-(D14-K)") (class "Default")
      (node (ref "D14") (pin "2") (pinfunction "K_2") (pintype "passive"))
      (node (ref "R37") (pin "1") (pinfunction "1_1") (pintype "passive"))
      (node (ref "U9") (pin "7") (pinfunction "HO_7") (pintype "passive"))
    )
    (net (code "25") (name "Net-(D15-A)") (class "Default")
      (node (ref "D15") (pin "1") (pinfunction "A_1") (pintype "passive"))
      (node (ref "R38") (pin "2") (pinfunction "2_2") (pintype "passive"))
      (node (ref "R40") (pin "2") (pinfunction "2_2") (pintype "passive"))
      (node (ref "T5") (pin "1") (pinfunction "G_1") (pintype "passive"))
    )
    (net (code "26") (name "Net-(D15-K)") (class "Default")
      (node (ref "D15") (pin "2") (pinfunction "K_2") (pintype "passive"))
      (node (ref "R38") (pin "1") (pinfunction "1_1") (pintype "passive"))
      (node (ref "U10") (pin "7") (pinfunction "HO_7") (pintype "passive"))
    )
    (net (code "27") (name "Net-(D18-A)") (class "Default")
      (node (ref "D18") (pin "1") (pinfunction "A_1") (pintype "passive"))
      (node (ref "R41") (pin "2") (pinfunction "2_2") (pintype "passive"))
      (node (ref "R43") (pin "2") (pinfunction "2_2") (pintype "passive"))
      (node (ref "T8") (pin "1") (pinfunction "G_1") (pintype "passive"))
    )
    (net (code "28") (name "Net-(D18-K)") (class "Default")
      (node (ref "D18") (pin "2") (pinfunction "K_2") (pintype "passive"))
      (node (ref "R41") (pin "1") (pinfunction "1_1") (pintype "passive"))
      (node (ref "U9") (pin "5") (pinfunction "LO_5") (pintype "passive"))
    )
    (net (code "29") (name "Net-(D19-A)") (class "Default")
      (node (ref "D19") (pin "1") (pinfunction "A_1") (pintype "passive"))
      (node (ref "R42") (pin "2") (pinfunction "2_2") (pintype "passive"))
      (node (ref "R44") (pin "2") (pinfunction "2_2") (pintype "passive"))
      (node (ref "T7") (pin "1") (pinfunction "G_1") (pintype "passive"))
    )
    (net (code "30") (name "Net-(D19-K)") (class "Default")
      (node (ref "D19") (pin "2") (pinfunction "K_2") (pintype "passive"))
      (node (ref "R42") (pin "1") (pinfunction "1_1") (pintype "passive"))
      (node (ref "U10") (pin "5") (pinfunction "LO_5") (pintype "passive"))
    )
    (net (code "31") (name "Net-(LED1-A)") (class "Default")
      (node (ref "LED1") (pin "1") (pinfunction "A_1") (pintype "passive"))
      (node (ref "R1") (pin "2") (pinfunction "2_2") (pintype "passive"))
    )
    (net (code "32") (name "Net-(LED4-A)") (class "Default")
      (node (ref "LED4") (pin "1") (pinfunction "A_1") (pintype "passive"))
      (node (ref "R7") (pin "2") (pinfunction "2_2") (pintype "passive"))
    )
    (net (code "33") (name "Net-(LED5-A)") (class "Default")
      (node (ref "LED5") (pin "1") (pinfunction "A_1") (pintype "passive"))
      (node (ref "R5") (pin "2") (pinfunction "2_2") (pintype "passive"))
    )
    (net (code "34") (name "Net-(R2-Pad1)") (class "Default")
      (node (ref "R2") (pin "1") (pinfunction "1_1") (pintype "passive"))
      (node (ref "R3") (pin "1") (pinfunction "1_1") (pintype "passive"))
    )
    (net (code "35") (name "Net-(U3-FB)") (class "Default")
      (node (ref "R3") (pin "2") (pinfunction "2_2") (pintype "passive"))
      (node (ref "R4") (pin "2") (pinfunction "2_2") (pintype "passive"))
      (node (ref "U3") (pin "3") (pinfunction "FB_3") (pintype "passive"))
    )
    (net (code "36") (name "Net-(U4-A0)") (class "Default")
      (node (ref "P1") (pin "4") (pinfunction "4_4") (pintype "passive"))
      (node (ref "U4") (pin "2") (pinfunction "A0_2") (pintype "passive"))
    )
    (net (code "37") (name "Net-(U4-A1)") (class "Default")
      (node (ref "P1") (pin "3") (pinfunction "3_3") (pintype "passive"))
      (node (ref "U4") (pin "3") (pinfunction "A1_3") (pintype "passive"))
    )
    (net (code "38") (name "Net-(U4-A2)") (class "Default")
      (node (ref "P1") (pin "2") (pinfunction "2_2") (pintype "passive"))
      (node (ref "U4") (pin "4") (pinfunction "A2_4") (pintype "passive"))
    )
    (net (code "39") (name "Net-(U4-A3)") (class "Default")
      (node (ref "P1") (pin "1") (pinfunction "1_1") (pintype "passive"))
      (node (ref "U4") (pin "5") (pinfunction "A3_5") (pintype "passive"))
    )
    (net (code "40") (name "PGND") (class "Default")
      (node (ref "C0") (pin "2") (pinfunction "2_2") (pintype "passive"))
      (node (ref "C1") (pin "1") (pinfunction "GND_1") (pintype "passive"))
      (node (ref "R0") (pin "2") (pinfunction "2_2") (pintype "passive"))
    )
    (net (code "41") (name "VCC_3V3") (class "Default")
      (node (ref "C12") (pin "2") (pinfunction "2_2") (pintype "passive"))
      (node (ref "C15") (pin "2") (pinfunction "2_2") (pintype "passive"))
      (node (ref "C2") (pin "2") (pinfunction "2_2") (pintype "passive"))
      (node (ref "C5") (pin "2") (pinfunction "2_2") (pintype "passive"))
      (node (ref "R1") (pin "1") (pinfunction "1_1") (pintype "passive"))
      (node (ref "U2") (pin "2") (pinfunction "Vout_2") (pintype "passive"))
      (node (ref "U2") (pin "4") (pinfunction "Vout_4") (pintype "passive"))
      (node (ref "U4") (pin "1") (pinfunction "DIR_1") (pintype "passive"))
      (node (ref "U4") (pin "20") (pinfunction "VCC_20") (pintype "passive"))
    )
    (net (code "42") (name "VCC_5V") (class "Default")
      (node (ref "C11") (pin "2") (pinfunction "2_2") (pintype "passive"))
      (node (ref "C3") (pin "2") (pinfunction "2_2") (pintype "passive"))
      (node (ref "C4") (pin "2") (pinfunction "2_2") (pintype "passive"))
      (node (ref "C8") (pin "2") (pinfunction "2_2") (pintype "passive"))
      (node (ref "R7") (pin "1") (pinfunction "1_1") (pintype "passive"))
      (node (ref "U1") (pin "2") (pinfunction "Vout_2") (pintype "passive"))
      (node (ref "U1") (pin "4") (pinfunction "Vout_4") (pintype "passive"))
      (node (ref "U2") (pin "3") (pinfunction "Vin_3") (pintype "passive"))
    )
    (net (code "43") (name "VCC_12V") (class "Default")
      (node (ref "C16") (pin "2") (pinfunction "2_2") (pintype "passive"))
      (node (ref "C17") (pin "2") (pinfunction "2_2") (pintype "passive"))
      (node (ref "C26") (pin "2") (pinfunction "2_2") (pintype "passive"))
      (node (ref "C27") (pin "2") (pinfunction "2_2") (pintype "passive"))
      (node (ref "C6") (pin "2") (pinfunction "2_2") (pintype "passive"))
      (node (ref "C7") (pin "2") (pinfunction "2_2") (pintype "passive"))
      (node (ref "D1") (pin "2") (pinfunction "K_2") (pintype "passive"))
      (node (ref "D12") (pin "1") (pinfunction "A_1") (pintype "passive"))
      (node (ref "D13") (pin "1") (pinfunction "A_1") (pintype "passive"))
      (node (ref "D2") (pin "1") (pinfunction "A_1") (pintype "passive"))
      (node (ref "D3") (pin "1") (pinfunction "A_1") (pintype "passive"))
      (node (ref "R2") (pin "2") (pinfunction "2_2") (pintype "passive"))
      (node (ref "R5") (pin "1") (pinfunction "1_1") (pintype "passive"))
      (node (ref "U10") (pin "1") (pinfunction "VCC_1") (pintype "passive"))
      (node (ref "U10") (pin "3") (pinfunction "SD_3") (pintype "passive"))
      (node (ref "U6") (pin "1") (pinfunction "VCC_1") (pintype "passive"))
      (node (ref "U6") (pin "3") (pinfunction "SD_3") (pintype "passive"))
      (node (ref "U7") (pin "1") (pinfunction "VCC_1") (pintype "passive"))
      (node (ref "U7") (pin "3") (pinfunction "SD_3") (pintype "passive"))
      (node (ref "U9") (pin "1") (pinfunction "VCC_1") (pintype "passive"))
      (node (ref "U9") (pin "3") (pinfunction "SD_3") (pintype "passive"))
    )
    (net (code "44") (name "VCC_BAT") (class "Default")
      (node (ref "C0") (pin "1") (pinfunction "1_1") (pintype "passive"))
      (node (ref "C1") (pin "2") (pinfunction "VCC_2") (pintype "passive"))
      (node (ref "C10") (pin "2") (pinfunction "2_2") (pintype "passive"))
      (node (ref "C18") (pin "2") (pinfunction "2_2") (pintype "passive"))
      (node (ref "C19") (pin "2") (pinfunction "2_2") (pintype "passive"))
      (node (ref "C9") (pin "2") (pinfunction "2_2") (pintype "passive"))
      (node (ref "D16") (pin "2") (pinfunction "K_2") (pintype "passive"))
      (node (ref "D17") (pin "2") (pinfunction "K_2") (pintype "passive"))
      (node (ref "D6") (pin "2") (pinfunction "K_2") (pintype "passive"))
      (node (ref "D7") (pin "2") (pinfunction "K_2") (pintype "passive"))
      (node (ref "L1") (pin "2") (pinfunction "2_2") (pintype "passive"))
      (node (ref "T1") (pin "2") (pinfunction "D_2") (pintype "passive"))
      (node (ref "T2") (pin "2") (pinfunction "D_2") (pintype "passive"))
      (node (ref "T5") (pin "2") (pinfunction "D_2") (pintype "passive"))
      (node (ref "T6") (pin "2") (pinfunction "D_2") (pintype "passive"))
      (node (ref "U1") (pin "3") (pinfunction "Vin_3") (pintype "passive"))
      (node (ref "U3") (pin "4") (pinfunction "EN_4") (pintype "passive"))
      (node (ref "U3") (pin "5") (pinfunction "Vin_5") (pintype "passive"))
    )
    (net (code "45") (name "unconnected-(P1-Pad5)") (class "Default")
      (node (ref "P1") (pin "5") (pinfunction "5_5") (pintype "passive+no_connect"))
    )
    (net (code "46") (name "unconnected-(P1-Pad6)") (class "Default")
      (node (ref "P1") (pin "6") (pinfunction "6_6") (pintype "passive+no_connect"))
    )
    (net (code "47") (name "unconnected-(U3-NC-Pad6)") (class "Default")
      (node (ref "U3") (pin "6") (pinfunction "NC_6") (pintype "passive+no_connect"))
    )
  )
)
